# 5-Pads.net
KiCad netlist of a schematic drawn in Altium Designer
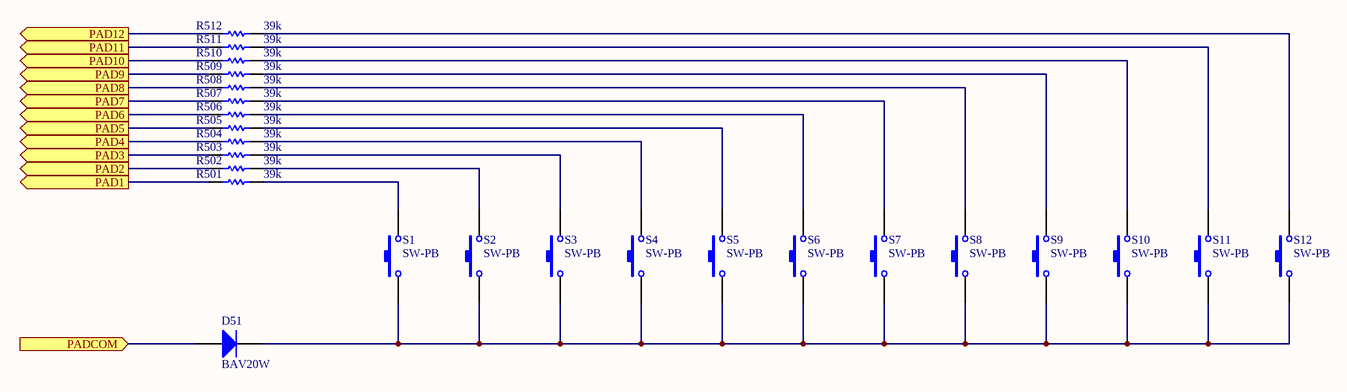
[diagram p0: 5-Pads.SchDoc]

(export (version "E")
  (design (tool "Eeschema 10.0.6"))
  (components
    (comp (ref "D51")
      (value "BAV20W")
      (footprint "Diode SOD-123")
      (description "Default Diode")
      (libsource (lib "Miscellaneous Devices") (part "Diode"))
    )
    (comp (ref "R501")
      (value "39k")
      (footprint "RES 1206")
      (description "Resistor")
      (libsource (lib "Miscellaneous Devices") (part "Res1"))
    )
    (comp (ref "R502")
      (value "39k")
      (footprint "RES 1206")
      (description "Resistor")
      (libsource (lib "Miscellaneous Devices") (part "Res1"))
    )
    (comp (ref "R503")
      (value "39k")
      (footprint "RES 1206")
      (description "Resistor")
      (libsource (lib "Miscellaneous Devices") (part "Res1"))
    )
    (comp (ref "R504")
      (value "39k")
      (footprint "RES 1206")
      (description "Resistor")
      (libsource (lib "Miscellaneous Devices") (part "Res1"))
    )
    (comp (ref "R505")
      (value "39k")
      (footprint "RES 1206")
      (description "Resistor")
      (libsource (lib "Miscellaneous Devices") (part "Res1"))
    )
    (comp (ref "R506")
      (value "39k")
      (footprint "RES 1206")
      (description "Resistor")
      (libsource (lib "Miscellaneous Devices") (part "Res1"))
    )
    (comp (ref "R507")
      (value "39k")
      (footprint "RES 1206")
      (description "Resistor")
      (libsource (lib "Miscellaneous Devices") (part "Res1"))
    )
    (comp (ref "R508")
      (value "39k")
      (footprint "RES 1206")
      (description "Resistor")
      (libsource (lib "Miscellaneous Devices") (part "Res1"))
    )
    (comp (ref "R509")
      (value "39k")
      (footprint "RES 1206")
      (description "Resistor")
      (libsource (lib "Miscellaneous Devices") (part "Res1"))
    )
    (comp (ref "R510")
      (value "39k")
      (footprint "RES 1206")
      (description "Resistor")
      (libsource (lib "Miscellaneous Devices") (part "Res1"))
    )
    (comp (ref "R511")
      (value "39k")
      (footprint "RES 1206")
      (description "Resistor")
      (libsource (lib "Miscellaneous Devices") (part "Res1"))
    )
    (comp (ref "R512")
      (value "39k")
      (footprint "RES 1206")
      (description "Resistor")
      (libsource (lib "Miscellaneous Devices") (part "Res1"))
    )
    (comp (ref "S1")
      (value "SW-PB")
      (footprint "PAD")
      (description "Switch")
      (libsource (lib "Miscellaneous Devices") (part "SW-PB"))
    )
    (comp (ref "S2")
      (value "SW-PB")
      (footprint "PAD")
      (description "Switch")
      (libsource (lib "Any") (part "SW-PB"))
    )
    (comp (ref "S3")
      (value "SW-PB")
      (footprint "PAD")
      (description "Switch")
      (libsource (lib "Any") (part "SW-PB"))
    )
    (comp (ref "S4")
      (value "SW-PB")
      (footprint "PAD")
      (description "Switch")
      (libsource (lib "Any") (part "SW-PB"))
    )
    (comp (ref "S5")
      (value "SW-PB")
      (footprint "PAD")
      (description "Switch")
      (libsource (lib "Any") (part "SW-PB"))
    )
    (comp (ref "S6")
      (value "SW-PB")
      (footprint "PAD")
      (description "Switch")
      (libsource (lib "Any") (part "SW-PB"))
    )
    (comp (ref "S7")
      (value "SW-PB")
      (footprint "PAD")
      (description "Switch")
      (libsource (lib "Any") (part "SW-PB"))
    )
    (comp (ref "S8")
      (value "SW-PB")
      (footprint "PAD")
      (description "Switch")
      (libsource (lib "Any") (part "SW-PB"))
    )
    (comp (ref "S9")
      (value "SW-PB")
      (footprint "PAD")
      (description "Switch")
      (libsource (lib "Any") (part "SW-PB"))
    )
    (comp (ref "S10")
      (value "SW-PB")
      (footprint "PAD")
      (description "Switch")
      (libsource (lib "Any") (part "SW-PB"))
    )
    (comp (ref "S11")
      (value "SW-PB")
      (footprint "PAD")
      (description "Switch")
      (libsource (lib "Any") (part "SW-PB"))
    )
    (comp (ref "S12")
      (value "SW-PB")
      (footprint "PAD")
      (description "Switch")
      (libsource (lib "Miscellaneous Devices") (part "SW-PB"))
    )
  )
  (nets
    (net (code "1") (name "/PAD1") (class "Default")
      (node (ref "R501") (pin "1") (pinfunction "1_1") (pintype "passive"))
    )
    (net (code "2") (name "/PAD2") (class "Default")
      (node (ref "R502") (pin "1") (pinfunction "1_1") (pintype "passive"))
    )
    (net (code "3") (name "/PAD3") (class "Default")
      (node (ref "R503") (pin "1") (pinfunction "1_1") (pintype "passive"))
    )
    (net (code "4") (name "/PAD4") (class "Default")
      (node (ref "R504") (pin "1") (pinfunction "1_1") (pintype "passive"))
    )
    (net (code "5") (name "/PAD5") (class "Default")
      (node (ref "R505") (pin "1") (pinfunction "1_1") (pintype "passive"))
    )
    (net (code "6") (name "/PAD6") (class "Default")
      (node (ref "R506") (pin "1") (pinfunction "1_1") (pintype "passive"))
    )
    (net (code "7") (name "/PAD7") (class "Default")
      (node (ref "R507") (pin "1") (pinfunction "1_1") (pintype "passive"))
    )
    (net (code "8") (name "/PAD8") (class "Default")
      (node (ref "R508") (pin "1") (pinfunction "1_1") (pintype "passive"))
    )
    (net (code "9") (name "/PAD9") (class "Default")
      (node (ref "R509") (pin "1") (pinfunction "1_1") (pintype "passive"))
    )
    (net (code "10") (name "/PAD10") (class "Default")
      (node (ref "R510") (pin "1") (pinfunction "1_1") (pintype "passive"))
    )
    (net (code "11") (name "/PAD11") (class "Default")
      (node (ref "R511") (pin "1") (pinfunction "1_1") (pintype "passive"))
    )
    (net (code "12") (name "/PAD12") (class "Default")
      (node (ref "R512") (pin "1") (pinfunction "1_1") (pintype "passive"))
    )
    (net (code "13") (name "/PADCOM") (class "Default")
      (node (ref "D51") (pin "1") (pinfunction "A_1") (pintype "passive"))
    )
    (net (code "14") (name "Net-(D51-K)") (class "Default")
      (node (ref "D51") (pin "2") (pinfunction "K_2") (pintype "passive"))
      (node (ref "S1") (pin "1") (pinfunction "1_1") (pintype "passive"))
      (node (ref "S10") (pin "1") (pinfunction "1_1") (pintype "passive"))
      (node (ref "S11") (pin "1") (pinfunction "1_1") (pintype "passive"))
      (node (ref "S12") (pin "1") (pinfunction "1_1") (pintype "passive"))
      (node (ref "S2") (pin "1") (pinfunction "1_1") (pintype "passive"))
      (node (ref "S3") (pin "1") (pinfunction "1_1") (pintype "passive"))
      (node (ref "S4") (pin "1") (pinfunction "1_1") (pintype "passive"))
      (node (ref "S5") (pin "1") (pinfunction "1_1") (pintype "passive"))
      (node (ref "S6") (pin "1") (pinfunction "1_1") (pintype "passive"))
      (node (ref "S7") (pin "1") (pinfunction "1_1") (pintype "passive"))
      (node (ref "S8") (pin "1") (pinfunction "1_1") (pintype "passive"))
      (node (ref "S9") (pin "1") (pinfunction "1_1") (pintype "passive"))
    )
    (net (code "15") (name "Net-(R501-Pad2)") (class "Default")
      (node (ref "R501") (pin "2") (pinfunction "2_2") (pintype "passive"))
      (node (ref "S1") (pin "2") (pinfunction "2_2") (pintype "passive"))
    )
    (net (code "16") (name "Net-(R502-Pad2)") (class "Default")
      (node (ref "R502") (pin "2") (pinfunction "2_2") (pintype "passive"))
      (node (ref "S2") (pin "2") (pinfunction "2_2") (pintype "passive"))
    )
    (net (code "17") (name "Net-(R503-Pad2)") (class "Default")
      (node (ref "R503") (pin "2") (pinfunction "2_2") (pintype "passive"))
      (node (ref "S3") (pin "2") (pinfunction "2_2") (pintype "passive"))
    )
    (net (code "18") (name "Net-(R504-Pad2)") (class "Default")
      (node (ref "R504") (pin "2") (pinfunction "2_2") (pintype "passive"))
      (node (ref "S4") (pin "2") (pinfunction "2_2") (pintype "passive"))
    )
    (net (code "19") (name "Net-(R505-Pad2)") (class "Default")
      (node (ref "R505") (pin "2") (pinfunction "2_2") (pintype "passive"))
      (node (ref "S5") (pin "2") (pinfunction "2_2") (pintype "passive"))
    )
    (net (code "20") (name "Net-(R506-Pad2)") (class "Default")
      (node (ref "R506") (pin "2") (pinfunction "2_2") (pintype "passive"))
      (node (ref "S6") (pin "2") (pinfunction "2_2") (pintype "passive"))
    )
    (net (code "21") (name "Net-(R507-Pad2)") (class "Default")
      (node (ref "R507") (pin "2") (pinfunction "2_2") (pintype "passive"))
      (node (ref "S7") (pin "2") (pinfunction "2_2") (pintype "passive"))
    )
    (net (code "22") (name "Net-(R508-Pad2)") (class "Default")
      (node (ref "R508") (pin "2") (pinfunction "2_2") (pintype "passive"))
      (node (ref "S8") (pin "2") (pinfunction "2_2") (pintype "passive"))
    )
    (net (code "23") (name "Net-(R509-Pad2)") (class "Default")
      (node (ref "R509") (pin "2") (pinfunction "2_2") (pintype "passive"))
      (node (ref "S9") (pin "2") (pinfunction "2_2") (pintype "passive"))
    )
    (net (code "24") (name "Net-(R510-Pad2)") (class "Default")
      (node (ref "R510") (pin "2") (pinfunction "2_2") (pintype "passive"))
      (node (ref "S10") (pin "2") (pinfunction "2_2") (pintype "passive"))
    )
    (net (code "25") (name "Net-(R511-Pad2)") (class "Default")
      (node (ref "R511") (pin "2") (pinfunction "2_2") (pintype "passive"))
      (node (ref "S11") (pin "2") (pinfunction "2_2") (pintype "passive"))
    )
    (net (code "26") (name "Net-(R512-Pad2)") (class "Default")
      (node (ref "R512") (pin "2") (pinfunction "2_2") (pintype "passive"))
      (node (ref "S12") (pin "2") (pinfunction "2_2") (pintype "passive"))
    )
  )
)
